# schematic.net
KiCad netlist of a schematic drawn in EAGLE
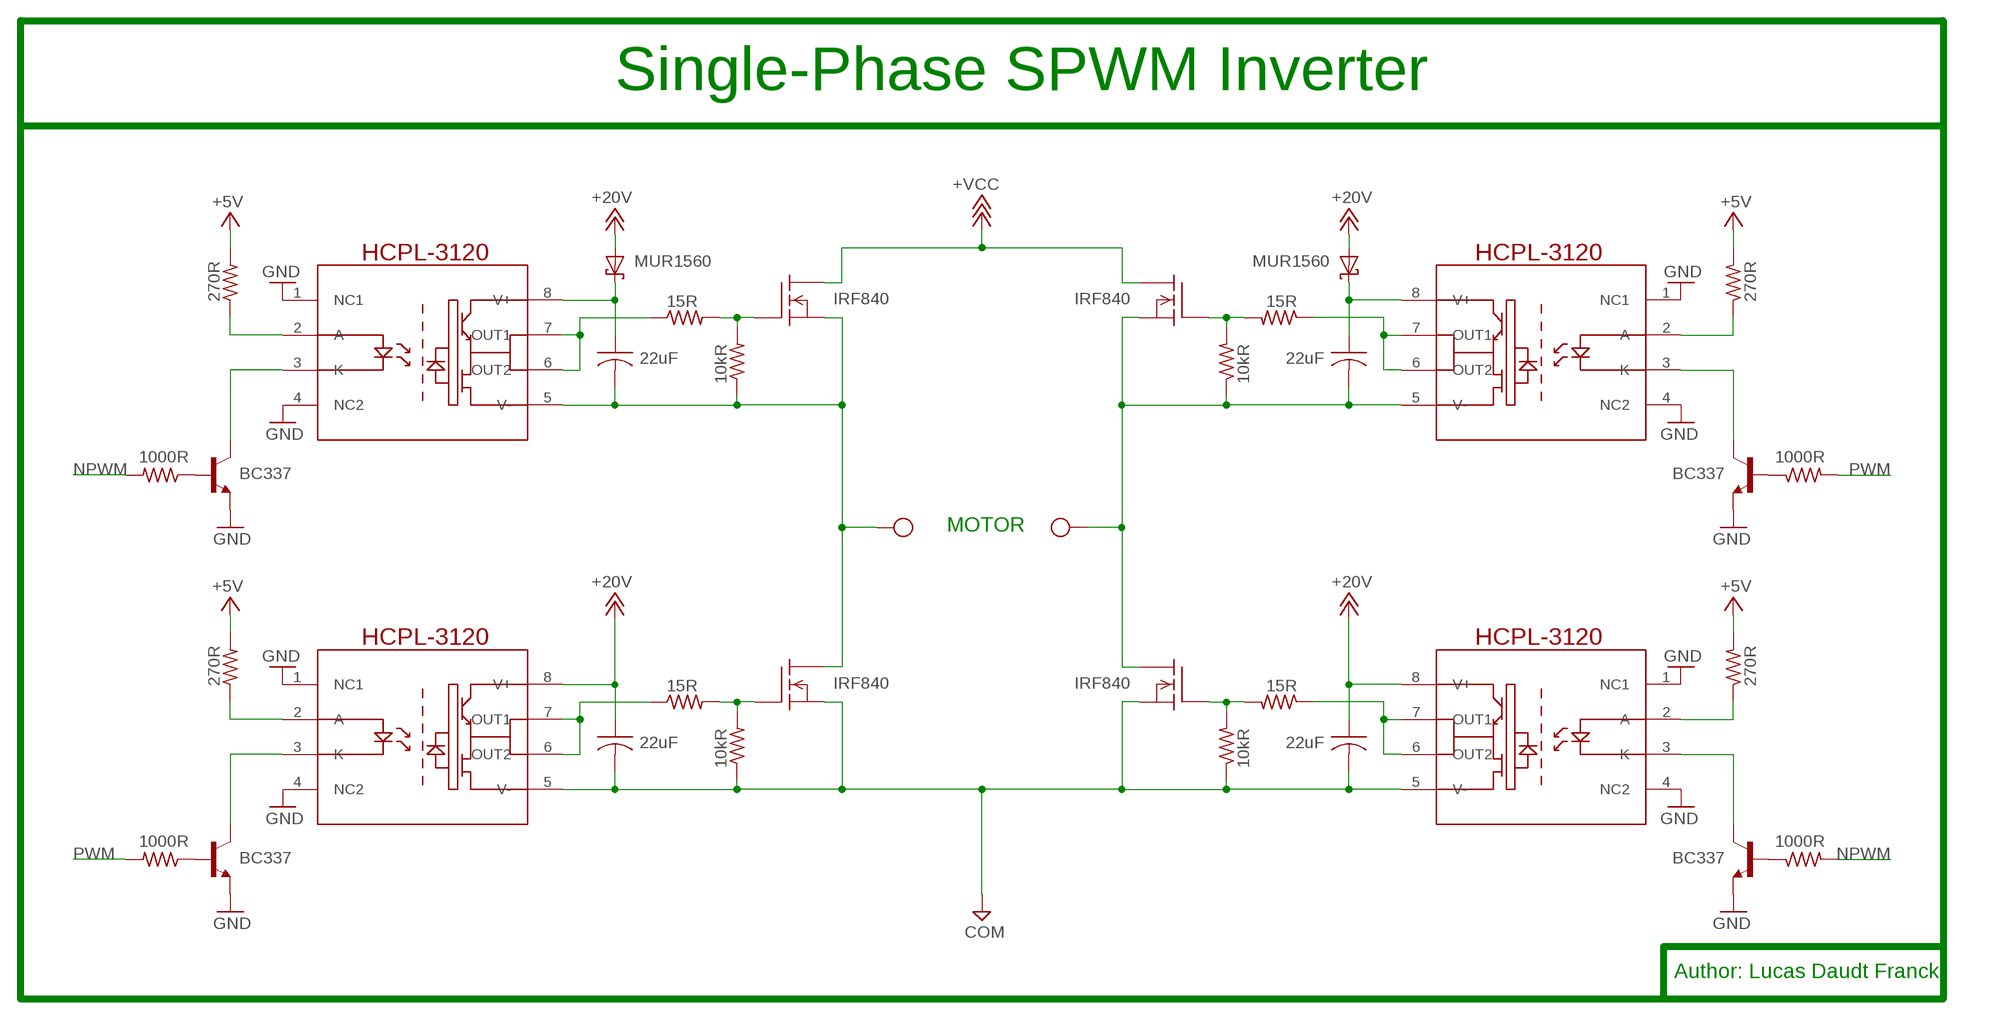
[diagram p0: schematic, sheet 1]

(export (version "E")
  (design (tool "Eeschema 10.0.6"))
  (components
    (comp (ref "C1")
      (value "22uF")
      (footprint "eagle-import:C025-024X044")
      (libsource (lib "eagle-import") (part "C-US025-024X044"))
    )
    (comp (ref "C2")
      (value "22uF")
      (footprint "eagle-import:C025-024X044")
      (libsource (lib "eagle-import") (part "C-US025-024X044"))
    )
    (comp (ref "C3")
      (value "22uF")
      (footprint "eagle-import:C025-024X044")
      (libsource (lib "eagle-import") (part "C-US025-024X044"))
    )
    (comp (ref "C4")
      (value "22uF")
      (footprint "eagle-import:C025-024X044")
      (libsource (lib "eagle-import") (part "C-US025-024X044"))
    )
    (comp (ref "D1")
      (value "MUR1560")
      (footprint "eagle-import:DO41-7.6")
      (libsource (lib "eagle-import") (part "1N5819-T"))
    )
    (comp (ref "D2")
      (value "MUR1560")
      (footprint "eagle-import:DO41-7.6")
      (libsource (lib "eagle-import") (part "1N5819-T"))
    )
    (comp (ref "Q1")
      (value "IRF840")
      (footprint "eagle-import:TO220")
      (libsource (lib "eagle-import") (part "IRF840"))
    )
    (comp (ref "Q2")
      (value "IRF840")
      (footprint "eagle-import:TO220")
      (libsource (lib "eagle-import") (part "IRF840"))
    )
    (comp (ref "Q3")
      (value "IRF840")
      (footprint "eagle-import:TO220")
      (libsource (lib "eagle-import") (part "IRF840"))
    )
    (comp (ref "Q4")
      (value "IRF840")
      (footprint "eagle-import:TO220")
      (libsource (lib "eagle-import") (part "IRF840"))
    )
    (comp (ref "R1")
      (value "270R")
      (footprint "eagle-import:0204_7")
      (libsource (lib "eagle-import") (part "R-US_0204/7"))
    )
    (comp (ref "R2")
      (value "15R")
      (footprint "eagle-import:0204_7")
      (libsource (lib "eagle-import") (part "R-US_0204/7"))
    )
    (comp (ref "R3")
      (value "1000R")
      (footprint "eagle-import:0204_7")
      (libsource (lib "eagle-import") (part "R-US_0204/7"))
    )
    (comp (ref "R4")
      (value "10kR")
      (footprint "eagle-import:0204_7")
      (libsource (lib "eagle-import") (part "R-US_0204/7"))
    )
    (comp (ref "R5")
      (value "270R")
      (footprint "eagle-import:0204_7")
      (libsource (lib "eagle-import") (part "R-US_0204/7"))
    )
    (comp (ref "R6")
      (value "1000R")
      (footprint "eagle-import:0204_7")
      (libsource (lib "eagle-import") (part "R-US_0204/7"))
    )
    (comp (ref "R7")
      (value "15R")
      (footprint "eagle-import:0204_7")
      (libsource (lib "eagle-import") (part "R-US_0204/7"))
    )
    (comp (ref "R8")
      (value "10kR")
      (footprint "eagle-import:0204_7")
      (libsource (lib "eagle-import") (part "R-US_0204/7"))
    )
    (comp (ref "R9")
      (value "270R")
      (footprint "eagle-import:0204_7")
      (libsource (lib "eagle-import") (part "R-US_0204/7"))
    )
    (comp (ref "R10")
      (value "1000R")
      (footprint "eagle-import:0204_7")
      (libsource (lib "eagle-import") (part "R-US_0204/7"))
    )
    (comp (ref "R11")
      (value "15R")
      (footprint "eagle-import:0204_7")
      (libsource (lib "eagle-import") (part "R-US_0204/7"))
    )
    (comp (ref "R12")
      (value "10kR")
      (footprint "eagle-import:0204_7")
      (libsource (lib "eagle-import") (part "R-US_0204/7"))
    )
    (comp (ref "R13")
      (value "270R")
      (footprint "eagle-import:0204_7")
      (libsource (lib "eagle-import") (part "R-US_0204/7"))
    )
    (comp (ref "R14")
      (value "1000R")
      (footprint "eagle-import:0204_7")
      (libsource (lib "eagle-import") (part "R-US_0204/7"))
    )
    (comp (ref "R15")
      (value "15R")
      (footprint "eagle-import:0204_7")
      (libsource (lib "eagle-import") (part "R-US_0204/7"))
    )
    (comp (ref "R16")
      (value "10kR")
      (footprint "eagle-import:0204_7")
      (libsource (lib "eagle-import") (part "R-US_0204/7"))
    )
    (comp (ref "T1")
      (value "BC337")
      (footprint "eagle-import:TO92")
      (libsource (lib "eagle-import") (part "BC337"))
    )
    (comp (ref "T2")
      (value "BC337")
      (footprint "eagle-import:TO92")
      (libsource (lib "eagle-import") (part "BC337"))
    )
    (comp (ref "T3")
      (value "BC337")
      (footprint "eagle-import:TO92")
      (libsource (lib "eagle-import") (part "BC337"))
    )
    (comp (ref "T4")
      (value "BC337")
      (footprint "eagle-import:TO92")
      (libsource (lib "eagle-import") (part "BC337"))
    )
    (comp (ref "U1")
      (value "HCPL-3120")
      (footprint "eagle-import:SMD8")
      (libsource (lib "eagle-import") (part "HCPL-3120SMD"))
    )
    (comp (ref "U2")
      (value "HCPL-3120")
      (footprint "eagle-import:SMD8")
      (libsource (lib "eagle-import") (part "HCPL-3120SMD"))
    )
    (comp (ref "U3")
      (value "HCPL-3120")
      (footprint "eagle-import:SMD8")
      (libsource (lib "eagle-import") (part "HCPL-3120SMD"))
    )
    (comp (ref "U4")
      (value "HCPL-3120")
      (footprint "eagle-import:SMD8")
      (libsource (lib "eagle-import") (part "HCPL-3120SMD"))
    )
    (comp (ref "X1")
      (value "AK300/2")
      (footprint "eagle-import:AK300_2")
      (libsource (lib "eagle-import") (part "AK300/2"))
    )
  )
  (nets
    (net (code "1") (name "+5V") (class "Default")
      (node (ref "R1") (pin "2") (pinfunction "2_2") (pintype "passive"))
      (node (ref "R13") (pin "2") (pinfunction "2_2") (pintype "passive"))
      (node (ref "R5") (pin "2") (pinfunction "2_2") (pintype "passive"))
      (node (ref "R9") (pin "2") (pinfunction "2_2") (pintype "passive"))
    )
    (net (code "2") (name "+20V") (class "Default")
      (node (ref "C1") (pin "1") (pinfunction "1_1") (pintype "passive"))
      (node (ref "C3") (pin "1") (pinfunction "1_1") (pintype "passive"))
      (node (ref "D1") (pin "A") (pinfunction "A_A") (pintype "passive"))
      (node (ref "D2") (pin "A") (pinfunction "A_A") (pintype "passive"))
      (node (ref "U1") (pin "8") (pinfunction "V+_8") (pintype "bidirectional"))
      (node (ref "U3") (pin "8") (pinfunction "V+_8") (pintype "bidirectional"))
    )
    (net (code "3") (name "+VCC") (class "Default")
      (node (ref "Q2") (pin "2") (pinfunction "D_2") (pintype "passive"))
      (node (ref "Q4") (pin "2") (pinfunction "D_2") (pintype "passive"))
    )
    (net (code "4") (name "/NPWM") (class "Default")
      (node (ref "R10") (pin "2") (pinfunction "2_2") (pintype "passive"))
      (node (ref "R6") (pin "2") (pinfunction "2_2") (pintype "passive"))
    )
    (net (code "5") (name "/PWM") (class "Default")
      (node (ref "R14") (pin "2") (pinfunction "2_2") (pintype "passive"))
      (node (ref "R3") (pin "2") (pinfunction "2_2") (pintype "passive"))
    )
    (net (code "6") (name "COM") (class "Default")
      (node (ref "C1") (pin "2") (pinfunction "2_2") (pintype "passive"))
      (node (ref "C3") (pin "2") (pinfunction "2_2") (pintype "passive"))
      (node (ref "Q1") (pin "3") (pinfunction "S_3") (pintype "passive"))
      (node (ref "Q3") (pin "3") (pinfunction "S_3") (pintype "passive"))
      (node (ref "R12") (pin "1") (pinfunction "1_1") (pintype "passive"))
      (node (ref "R4") (pin "1") (pinfunction "1_1") (pintype "passive"))
      (node (ref "T1") (pin "1") (pinfunction "E_1") (pintype "passive"))
      (node (ref "T2") (pin "1") (pinfunction "E_1") (pintype "passive"))
      (node (ref "T3") (pin "1") (pinfunction "E_1") (pintype "passive"))
      (node (ref "T4") (pin "1") (pinfunction "E_1") (pintype "passive"))
      (node (ref "U1") (pin "1") (pinfunction "NC1_1") (pintype "bidirectional"))
      (node (ref "U1") (pin "4") (pinfunction "NC2_4") (pintype "bidirectional"))
      (node (ref "U1") (pin "5") (pinfunction "V-_5") (pintype "bidirectional"))
      (node (ref "U2") (pin "1") (pinfunction "NC1_1") (pintype "bidirectional"))
      (node (ref "U2") (pin "4") (pinfunction "NC2_4") (pintype "bidirectional"))
      (node (ref "U3") (pin "1") (pinfunction "NC1_1") (pintype "bidirectional"))
      (node (ref "U3") (pin "4") (pinfunction "NC2_4") (pintype "bidirectional"))
      (node (ref "U3") (pin "5") (pinfunction "V-_5") (pintype "bidirectional"))
      (node (ref "U4") (pin "1") (pinfunction "NC1_1") (pintype "bidirectional"))
      (node (ref "U4") (pin "4") (pinfunction "NC2_4") (pintype "bidirectional"))
    )
    (net (code "7") (name "Net-(Q1-D)") (class "Default")
      (node (ref "C2") (pin "2") (pinfunction "2_2") (pintype "passive"))
      (node (ref "Q1") (pin "2") (pinfunction "D_2") (pintype "passive"))
      (node (ref "Q2") (pin "3") (pinfunction "S_3") (pintype "passive"))
      (node (ref "R8") (pin "1") (pinfunction "1_1") (pintype "passive"))
      (node (ref "U2") (pin "5") (pinfunction "V-_5") (pintype "bidirectional"))
      (node (ref "X1") (pin "1") (pinfunction "KL_1") (pintype "passive"))
    )
    (net (code "8") (name "Net-(Q1-G)") (class "Default")
      (node (ref "Q1") (pin "1") (pinfunction "G_1") (pintype "passive"))
      (node (ref "R2") (pin "2") (pinfunction "2_2") (pintype "passive"))
      (node (ref "R4") (pin "2") (pinfunction "2_2") (pintype "passive"))
    )
    (net (code "9") (name "Net-(Q2-G)") (class "Default")
      (node (ref "Q2") (pin "1") (pinfunction "G_1") (pintype "passive"))
      (node (ref "R7") (pin "2") (pinfunction "2_2") (pintype "passive"))
      (node (ref "R8") (pin "2") (pinfunction "2_2") (pintype "passive"))
    )
    (net (code "10") (name "Net-(Q3-D)") (class "Default")
      (node (ref "C4") (pin "2") (pinfunction "2_2") (pintype "passive"))
      (node (ref "Q3") (pin "2") (pinfunction "D_2") (pintype "passive"))
      (node (ref "Q4") (pin "3") (pinfunction "S_3") (pintype "passive"))
      (node (ref "R16") (pin "1") (pinfunction "1_1") (pintype "passive"))
      (node (ref "U4") (pin "5") (pinfunction "V-_5") (pintype "bidirectional"))
      (node (ref "X1") (pin "2") (pinfunction "KL_2") (pintype "passive"))
    )
    (net (code "11") (name "Net-(Q3-G)") (class "Default")
      (node (ref "Q3") (pin "1") (pinfunction "G_1") (pintype "passive"))
      (node (ref "R11") (pin "2") (pinfunction "2_2") (pintype "passive"))
      (node (ref "R12") (pin "2") (pinfunction "2_2") (pintype "passive"))
    )
    (net (code "12") (name "Net-(Q4-G)") (class "Default")
      (node (ref "Q4") (pin "1") (pinfunction "G_1") (pintype "passive"))
      (node (ref "R15") (pin "2") (pinfunction "2_2") (pintype "passive"))
      (node (ref "R16") (pin "2") (pinfunction "2_2") (pintype "passive"))
    )
    (net (code "13") (name "Net-(T1-B)") (class "Default")
      (node (ref "R3") (pin "1") (pinfunction "1_1") (pintype "passive"))
      (node (ref "T1") (pin "2") (pinfunction "B_2") (pintype "passive"))
    )
    (net (code "14") (name "Net-(T1-C)") (class "Default")
      (node (ref "T1") (pin "3") (pinfunction "C_3") (pintype "passive"))
      (node (ref "U1") (pin "3") (pinfunction "K_3") (pintype "bidirectional"))
    )
    (net (code "15") (name "Net-(T2-B)") (class "Default")
      (node (ref "R6") (pin "1") (pinfunction "1_1") (pintype "passive"))
      (node (ref "T2") (pin "2") (pinfunction "B_2") (pintype "passive"))
    )
    (net (code "16") (name "Net-(T2-C)") (class "Default")
      (node (ref "T2") (pin "3") (pinfunction "C_3") (pintype "passive"))
      (node (ref "U2") (pin "3") (pinfunction "K_3") (pintype "bidirectional"))
    )
    (net (code "17") (name "Net-(T3-B)") (class "Default")
      (node (ref "R10") (pin "1") (pinfunction "1_1") (pintype "passive"))
      (node (ref "T3") (pin "2") (pinfunction "B_2") (pintype "passive"))
    )
    (net (code "18") (name "Net-(T3-C)") (class "Default")
      (node (ref "T3") (pin "3") (pinfunction "C_3") (pintype "passive"))
      (node (ref "U3") (pin "3") (pinfunction "K_3") (pintype "bidirectional"))
    )
    (net (code "19") (name "Net-(T4-B)") (class "Default")
      (node (ref "R14") (pin "1") (pinfunction "1_1") (pintype "passive"))
      (node (ref "T4") (pin "2") (pinfunction "B_2") (pintype "passive"))
    )
    (net (code "20") (name "Net-(T4-C)") (class "Default")
      (node (ref "T4") (pin "3") (pinfunction "C_3") (pintype "passive"))
      (node (ref "U4") (pin "3") (pinfunction "K_3") (pintype "bidirectional"))
    )
    (net (code "21") (name "Net-(U1-A)") (class "Default")
      (node (ref "R1") (pin "1") (pinfunction "1_1") (pintype "passive"))
      (node (ref "U1") (pin "2") (pinfunction "A_2") (pintype "bidirectional"))
    )
    (net (code "22") (name "Net-(U1-OUT1)") (class "Default")
      (node (ref "R2") (pin "1") (pinfunction "1_1") (pintype "passive"))
      (node (ref "U1") (pin "6") (pinfunction "OUT2_6") (pintype "bidirectional"))
      (node (ref "U1") (pin "7") (pinfunction "OUT1_7") (pintype "bidirectional"))
    )
    (net (code "23") (name "Net-(U2-A)") (class "Default")
      (node (ref "R5") (pin "1") (pinfunction "1_1") (pintype "passive"))
      (node (ref "U2") (pin "2") (pinfunction "A_2") (pintype "bidirectional"))
    )
    (net (code "24") (name "Net-(U2-OUT1)") (class "Default")
      (node (ref "R7") (pin "1") (pinfunction "1_1") (pintype "passive"))
      (node (ref "U2") (pin "6") (pinfunction "OUT2_6") (pintype "bidirectional"))
      (node (ref "U2") (pin "7") (pinfunction "OUT1_7") (pintype "bidirectional"))
    )
    (net (code "25") (name "Net-(U2-V+)") (class "Default")
      (node (ref "C2") (pin "1") (pinfunction "1_1") (pintype "passive"))
      (node (ref "D1") (pin "C") (pinfunction "C_C") (pintype "passive"))
      (node (ref "U2") (pin "8") (pinfunction "V+_8") (pintype "bidirectional"))
    )
    (net (code "26") (name "Net-(U3-A)") (class "Default")
      (node (ref "R9") (pin "1") (pinfunction "1_1") (pintype "passive"))
      (node (ref "U3") (pin "2") (pinfunction "A_2") (pintype "bidirectional"))
    )
    (net (code "27") (name "Net-(U3-OUT1)") (class "Default")
      (node (ref "R11") (pin "1") (pinfunction "1_1") (pintype "passive"))
      (node (ref "U3") (pin "6") (pinfunction "OUT2_6") (pintype "bidirectional"))
      (node (ref "U3") (pin "7") (pinfunction "OUT1_7") (pintype "bidirectional"))
    )
    (net (code "28") (name "Net-(U4-A)") (class "Default")
      (node (ref "R13") (pin "1") (pinfunction "1_1") (pintype "passive"))
      (node (ref "U4") (pin "2") (pinfunction "A_2") (pintype "bidirectional"))
    )
    (net (code "29") (name "Net-(U4-OUT1)") (class "Default")
      (node (ref "R15") (pin "1") (pinfunction "1_1") (pintype "passive"))
      (node (ref "U4") (pin "6") (pinfunction "OUT2_6") (pintype "bidirectional"))
      (node (ref "U4") (pin "7") (pinfunction "OUT1_7") (pintype "bidirectional"))
    )
    (net (code "30") (name "Net-(U4-V+)") (class "Default")
      (node (ref "C4") (pin "1") (pinfunction "1_1") (pintype "passive"))
      (node (ref "D2") (pin "C") (pinfunction "C_C") (pintype "passive"))
      (node (ref "U4") (pin "8") (pinfunction "V+_8") (pintype "bidirectional"))
    )
  )
)
